# SCH_New-Project_2024-11-16.net
KiCad netlist of a schematic drawn in EasyEDA
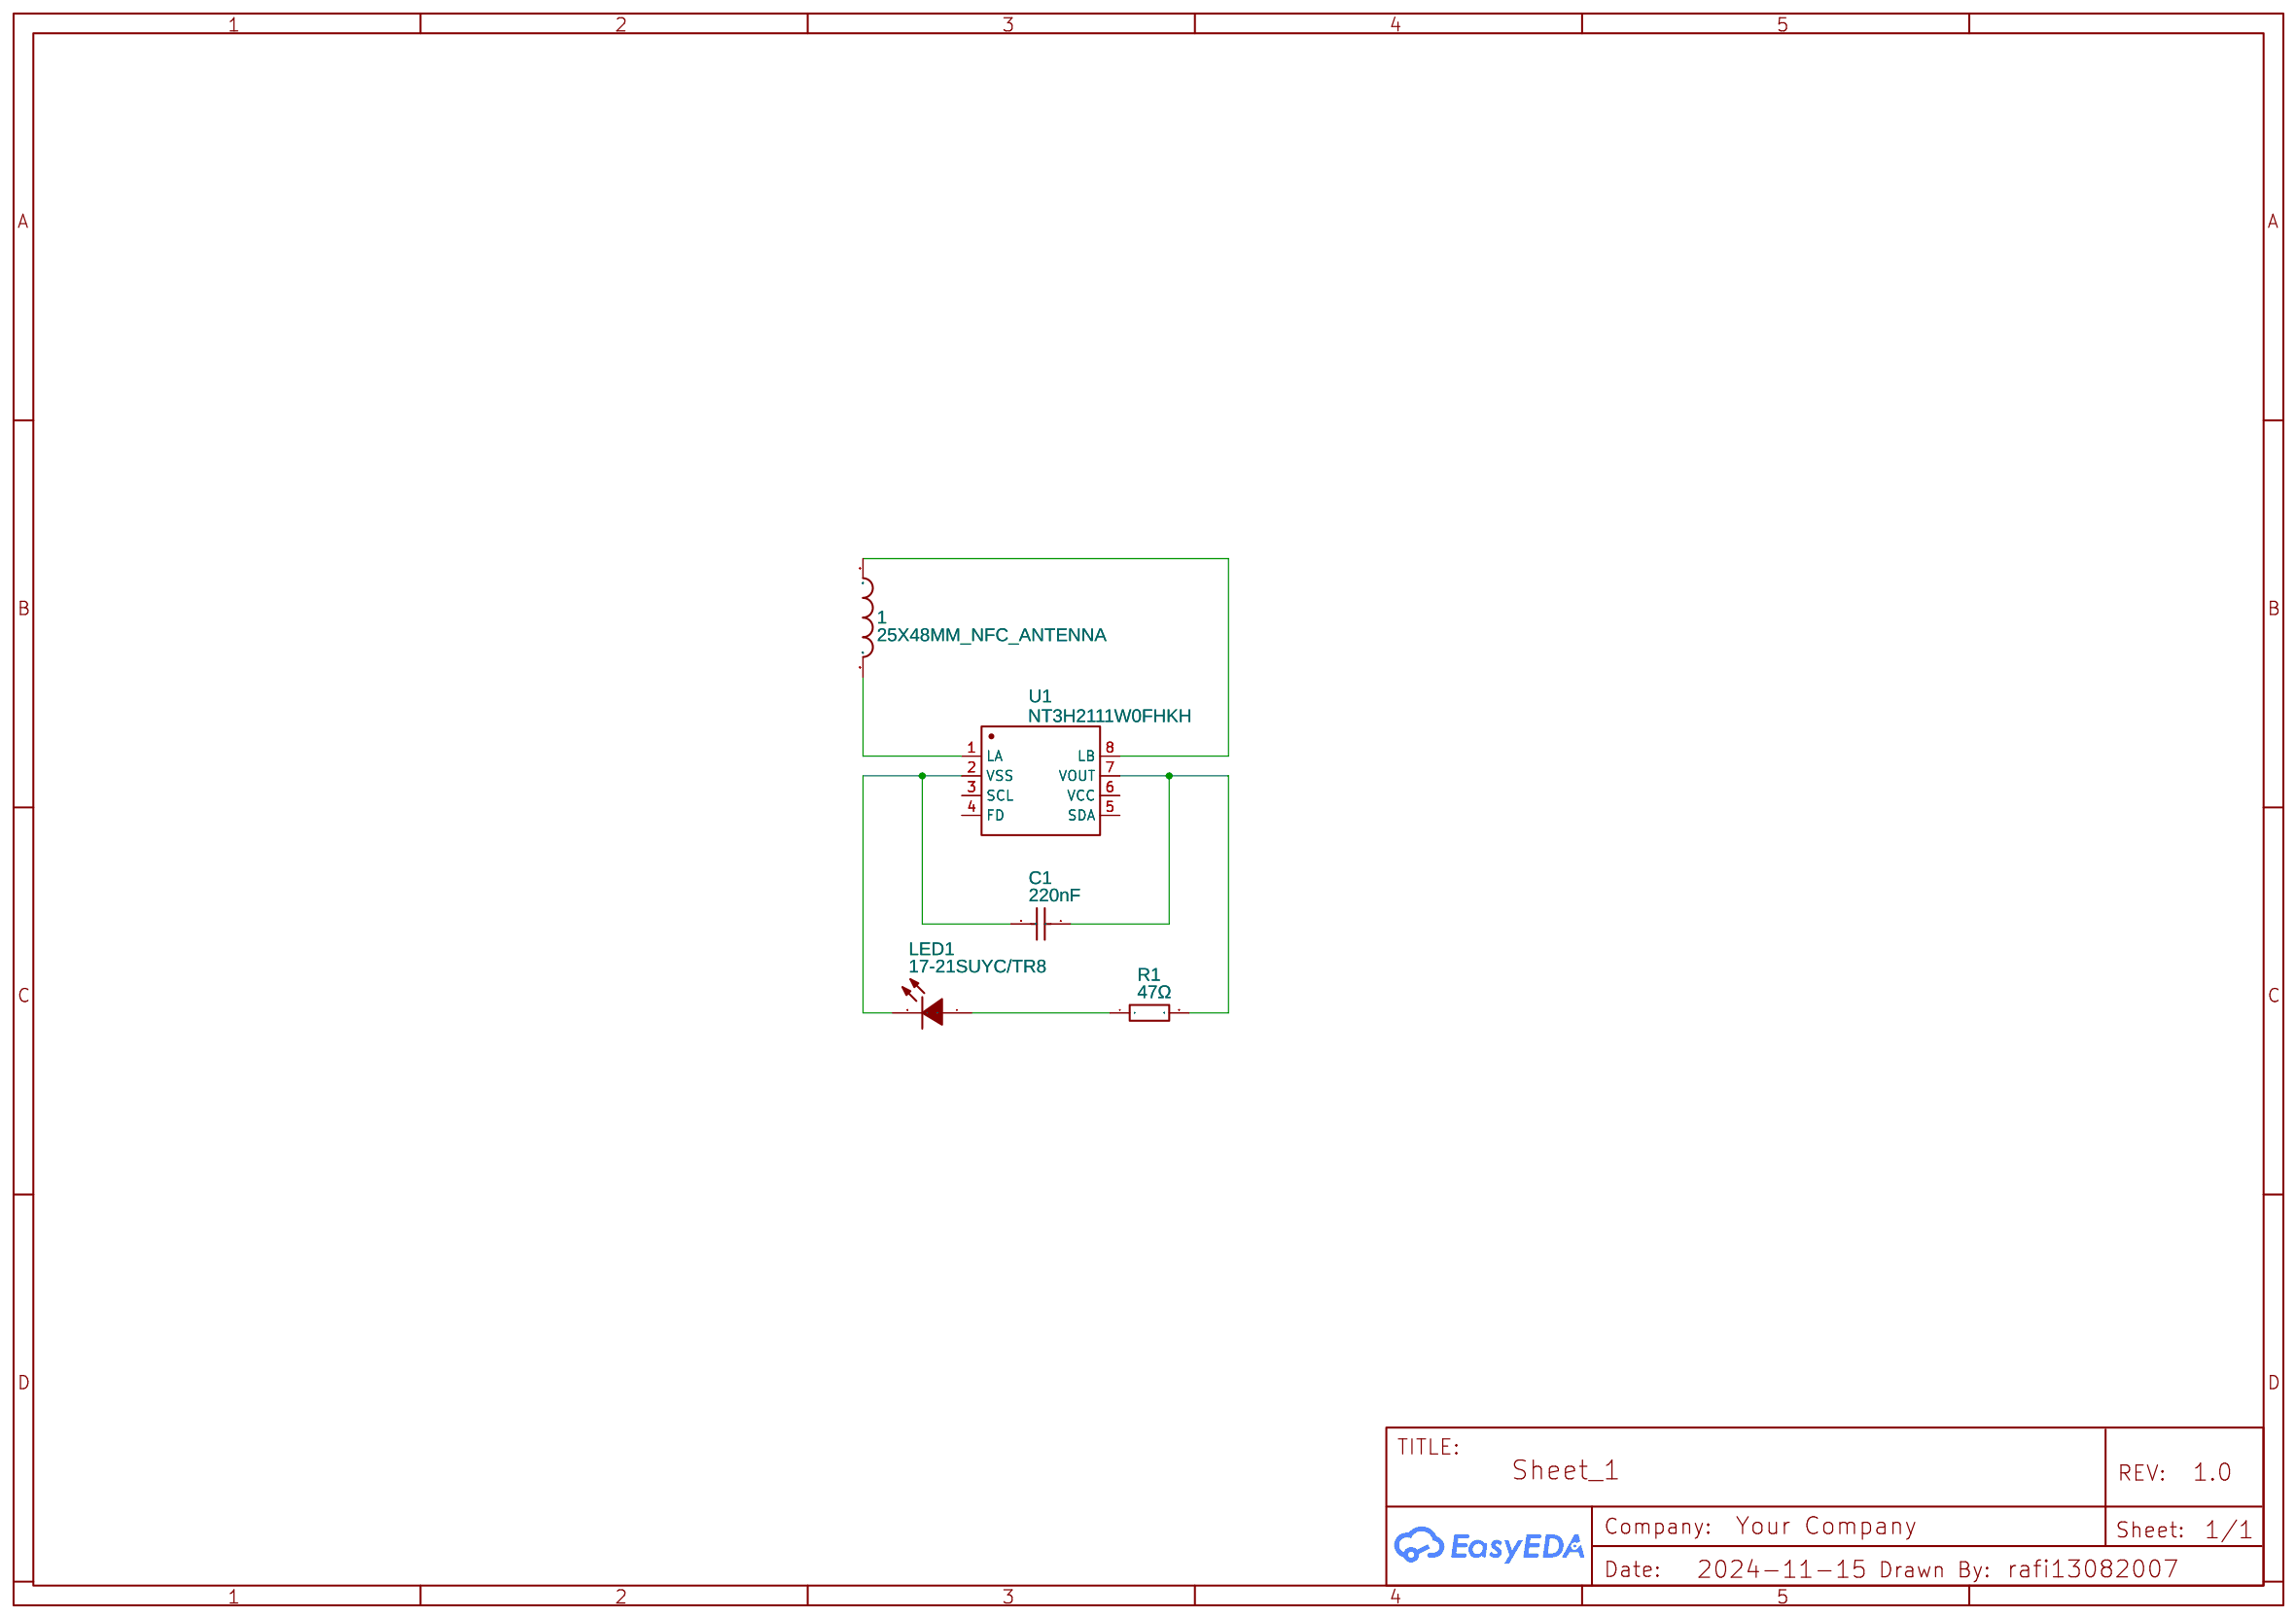
[diagram p0: schematic sheet]

(export (version "E")
  (design (tool "Eeschema 10.0.6"))
  (components
    (comp (ref "1") (value "25X48MM_NFC_ANTENNA") (libsource (lib "") (part "25X48MM_NFC_ANTENNA")))
    (comp (ref "C1")
      (value "220nF")
      (fields
        (field (name "Manufacturer Part") "CL10B224KA8NNNC")
        (field (name "Manufacturer") "SAMSUNG(三星)")
      )
      (libsource (lib "") (part "CL10B224KA8NNNC"))
    )
    (comp (ref "LED1")
      (value "17-21SUYC/TR8")
      (fields (field (name "Manufacturer Part") "KT-0805黄灯") (field (name "Manufacturer") "KENTO"))
      (libsource (lib "") (part "17-21SUYC/TR8"))
    )
    (comp (ref "R1")
      (value "47Ω")
      (fields
        (field (name "Manufacturer Part") "0603WAF470JT5E")
        (field (name "Manufacturer") "UNI-ROYAL(厚声)")
      )
      (libsource (lib "") (part "0603WAF470JT5E"))
    )
    (comp (ref "U1")
      (value "NT3H2111W0FHKH")
      (fields (field (name "Manufacturer") "NXP(恩智浦)"))
      (libsource (lib "") (part "NT3H2111W0FHKH"))
    )
  )
  (nets
    (net (code "1") (name "Net-(LED1-+)") (class "Default")
      (node (ref "LED1") (pin "1") (pinfunction "+_1") (pintype "unspecified"))
      (node (ref "R1") (pin "1") (pinfunction "1_1") (pintype "input"))
    )
    (net (code "2") (name "Net-(LED1--)") (class "Default")
      (node (ref "C1") (pin "1") (pinfunction "1_1") (pintype "input"))
      (node (ref "LED1") (pin "2") (pinfunction "-_2") (pintype "unspecified"))
      (node (ref "U1") (pin "2") (pinfunction "VSS_2") (pintype "unspecified"))
    )
    (net (code "3") (name "Net-(U1-LA)") (class "Default")
      (node (ref "1") (pin "P$2") (pinfunction "P$2_P$2") (pintype "bidirectional"))
      (node (ref "U1") (pin "1") (pinfunction "LA_1") (pintype "unspecified"))
    )
    (net (code "4") (name "Net-(U1-LB)") (class "Default")
      (node (ref "1") (pin "P$1") (pinfunction "P$1_P$1") (pintype "bidirectional"))
      (node (ref "U1") (pin "8") (pinfunction "LB_8") (pintype "unspecified"))
    )
    (net (code "5") (name "Net-(U1-VOUT)") (class "Default")
      (node (ref "C1") (pin "2") (pinfunction "2_2") (pintype "input"))
      (node (ref "R1") (pin "2") (pinfunction "2_2") (pintype "input"))
      (node (ref "U1") (pin "7") (pinfunction "VOUT_7") (pintype "unspecified"))
    )
    (net (code "6") (name "unconnected-(U1-FD-Pad4)") (class "Default")
      (node (ref "U1") (pin "4") (pinfunction "FD_4") (pintype "unspecified"))
    )
    (net (code "7") (name "unconnected-(U1-SCL-Pad3)") (class "Default")
      (node (ref "U1") (pin "3") (pinfunction "SCL_3") (pintype "unspecified"))
    )
    (net (code "8") (name "unconnected-(U1-SDA-Pad5)") (class "Default")
      (node (ref "U1") (pin "5") (pinfunction "SDA_5") (pintype "unspecified"))
    )
    (net (code "9") (name "unconnected-(U1-VCC-Pad6)") (class "Default")
      (node (ref "U1") (pin "6") (pinfunction "VCC_6") (pintype "unspecified"))
    )
  )
)
